# PMIC_Crystal.net
KiCad netlist of a schematic drawn in Altium Designer
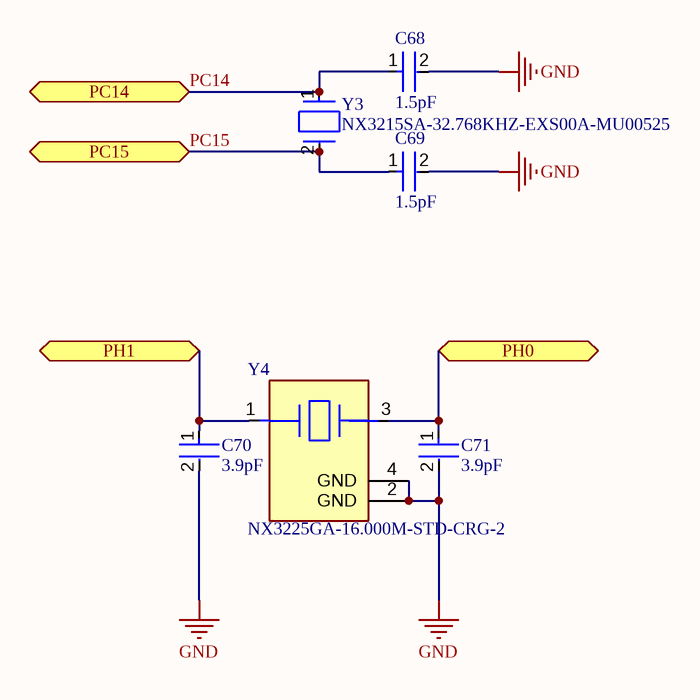
[diagram p0: PMIC_Crystal.SchDoc]

(export (version "E")
  (design (tool "Eeschema 10.0.6"))
  (components
    (comp (ref "C68")
      (value "1.5pF")
      (footprint "FP-C0603C-CF-MFG")
      (description "CAP CER 1.5PF 100V NP0 0603")
      (fields
        (field (name "MANUFACTURER PART NUMBER") "C0603C159C1GACTU")
        (field (name "TOLERANCE") "0.25 pF")
      )
      (libsource (lib "Altium Content Vault") (part "b4654b650e69147ec39a6b967a45e02"))
    )
    (comp (ref "C69")
      (value "1.5pF")
      (footprint "FP-C0603C-CF-MFG")
      (description "CAP CER 1.5PF 100V NP0 0603")
      (fields
        (field (name "MANUFACTURER PART NUMBER") "C0603C159C1GACTU")
        (field (name "TOLERANCE") "0.25 pF")
      )
      (libsource (lib "Altium Content Vault") (part "b4654b650e69147ec39a6b967a45e02"))
    )
    (comp (ref "C70")
      (value "3.9pF")
      (footprint "FP-CBR06C-MFG")
      (description "CAP CER 3.9PF 250V C0G/NP0 0603")
      (fields
        (field (name "OCTOPART") "https://octopart.com/cbr06c399cagac-kemet-20446767")
        (field (name "MANUFACTURER PART NUMBER") "CBR06C399CAGAC")
      )
      (libsource (lib "Altium Content Vault") (part "11868f565c42a9108669ba33697ecf6"))
    )
    (comp (ref "C71")
      (value "3.9pF")
      (footprint "FP-CBR06C-MFG")
      (description "CAP CER 3.9PF 250V C0G/NP0 0603")
      (fields
        (field (name "OCTOPART") "https://octopart.com/cbr06c399cagac-kemet-20446767")
        (field (name "MANUFACTURER PART NUMBER") "CBR06C399CAGAC")
      )
      (libsource (lib "Altium Content Vault") (part "11868f565c42a9108669ba33697ecf6"))
    )
    (comp (ref "Y3")
      (value "NX3215SA-32.768KHZ-EXS00A-MU00525")
      (footprint "FP-NX3215SA-MFG")
      (description "CRYSTAL 32.7680KHZ 6PF SMD")
      (libsource (lib "Altium Content Vault") (part "c23a69dc6c9e2f18f2079038eb95dd1"))
    )
    (comp (ref "Y4")
      (value "NX3225GA-16.000M-STD-CRG-2")
      (footprint "FP-NX3225GA-MFG")
      (description "CRYSTAL 16.0000MHZ 8PF SMD")
      (libsource (lib "Altium Content Vault") (part "6320effb7d3e443b36bf79d8ebe02e5"))
    )
  )
  (nets
    (net (code "1") (name "/PC14") (class "Default")
      (node (ref "C68") (pin "1") (pinfunction "1_1") (pintype "passive"))
      (node (ref "Y3") (pin "1") (pinfunction "1_1") (pintype "passive"))
    )
    (net (code "2") (name "/PC15") (class "Default")
      (node (ref "C69") (pin "1") (pinfunction "1_1") (pintype "passive"))
      (node (ref "Y3") (pin "2") (pinfunction "2_2") (pintype "passive"))
    )
    (net (code "3") (name "/PH0") (class "Default")
      (node (ref "C71") (pin "1") (pinfunction "1_1") (pintype "passive"))
      (node (ref "Y4") (pin "3") (pinfunction "3_3") (pintype "passive"))
    )
    (net (code "4") (name "/PH1") (class "Default")
      (node (ref "C70") (pin "1") (pinfunction "1_1") (pintype "passive"))
      (node (ref "Y4") (pin "1") (pinfunction "1_1") (pintype "passive"))
    )
    (net (code "5") (name "GND") (class "Default")
      (node (ref "C68") (pin "2") (pinfunction "2_2") (pintype "passive"))
      (node (ref "C69") (pin "2") (pinfunction "2_2") (pintype "passive"))
      (node (ref "C70") (pin "2") (pinfunction "2_2") (pintype "passive"))
      (node (ref "C71") (pin "2") (pinfunction "2_2") (pintype "passive"))
      (node (ref "Y4") (pin "2") (pinfunction "GND_2") (pintype "power_in"))
      (node (ref "Y4") (pin "4") (pinfunction "GND_4") (pintype "power_in"))
    )
  )
)
